# DEClampPanel.net
KiCad netlist of a schematic drawn in EAGLE
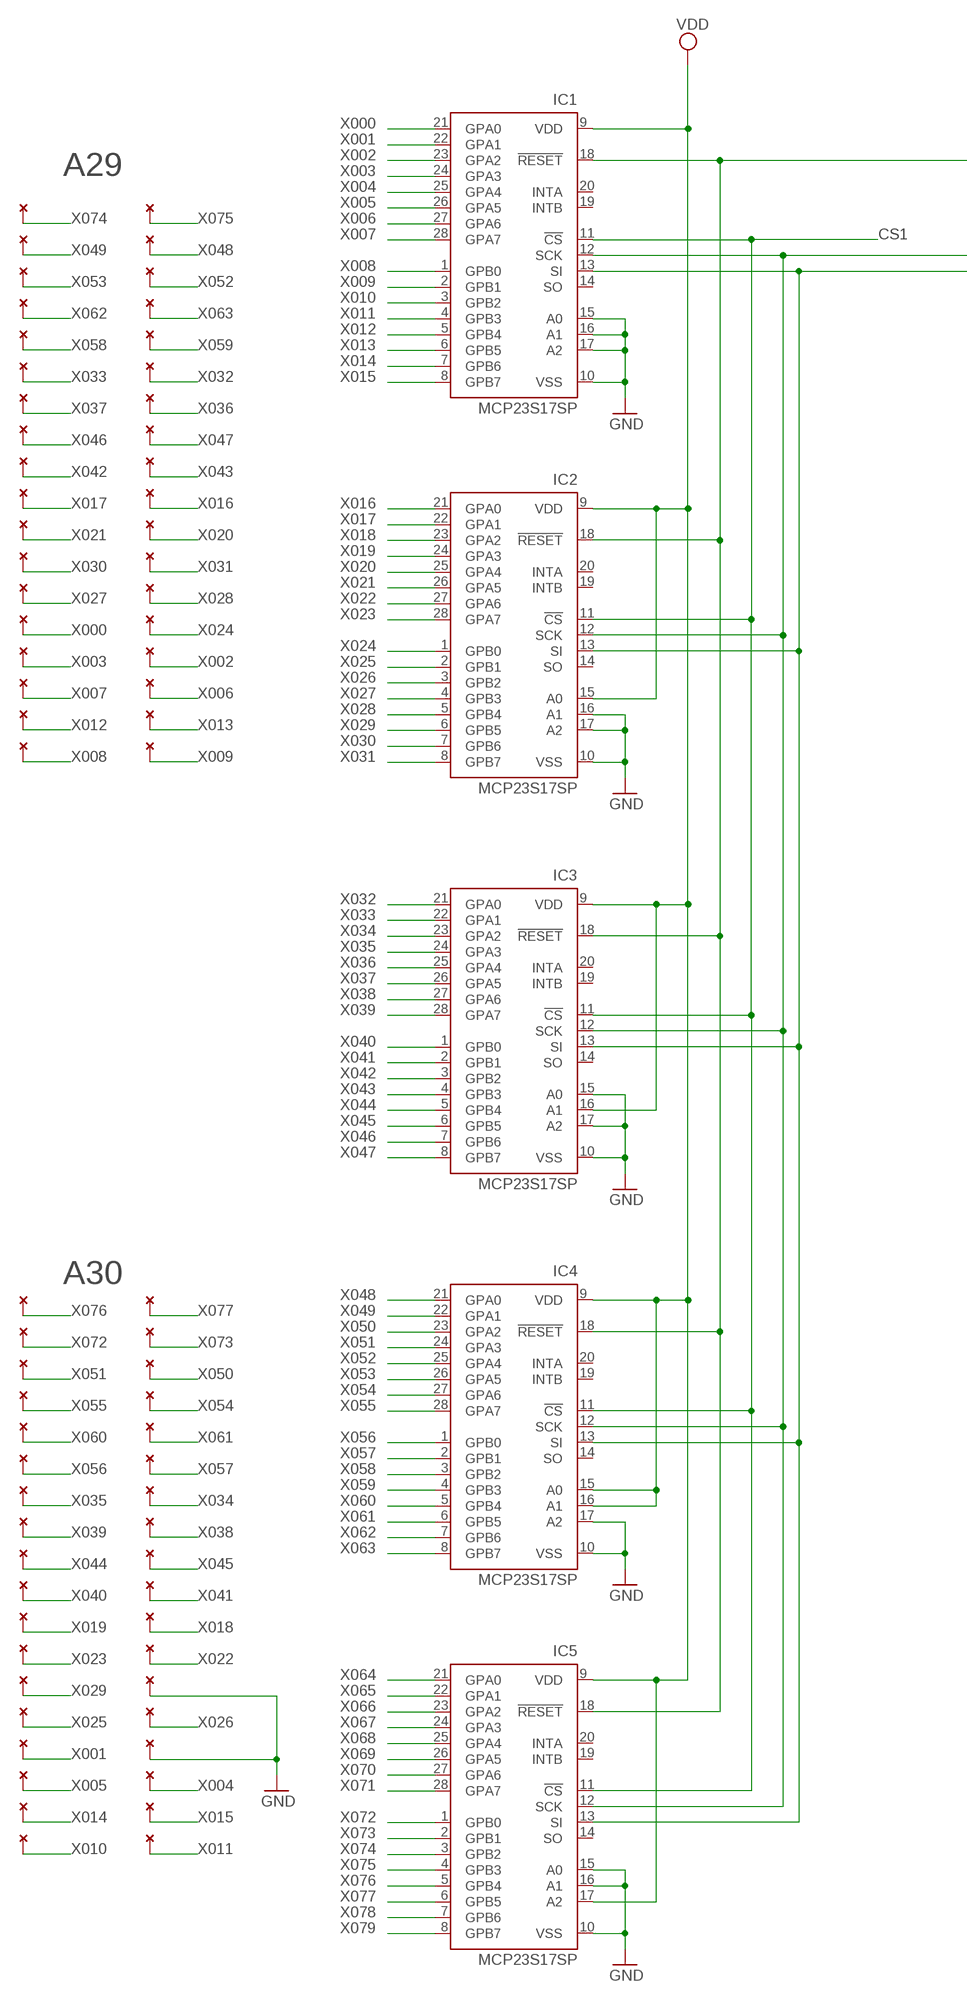
[diagram p0: schematic, sheet 1, part 1 of 2]
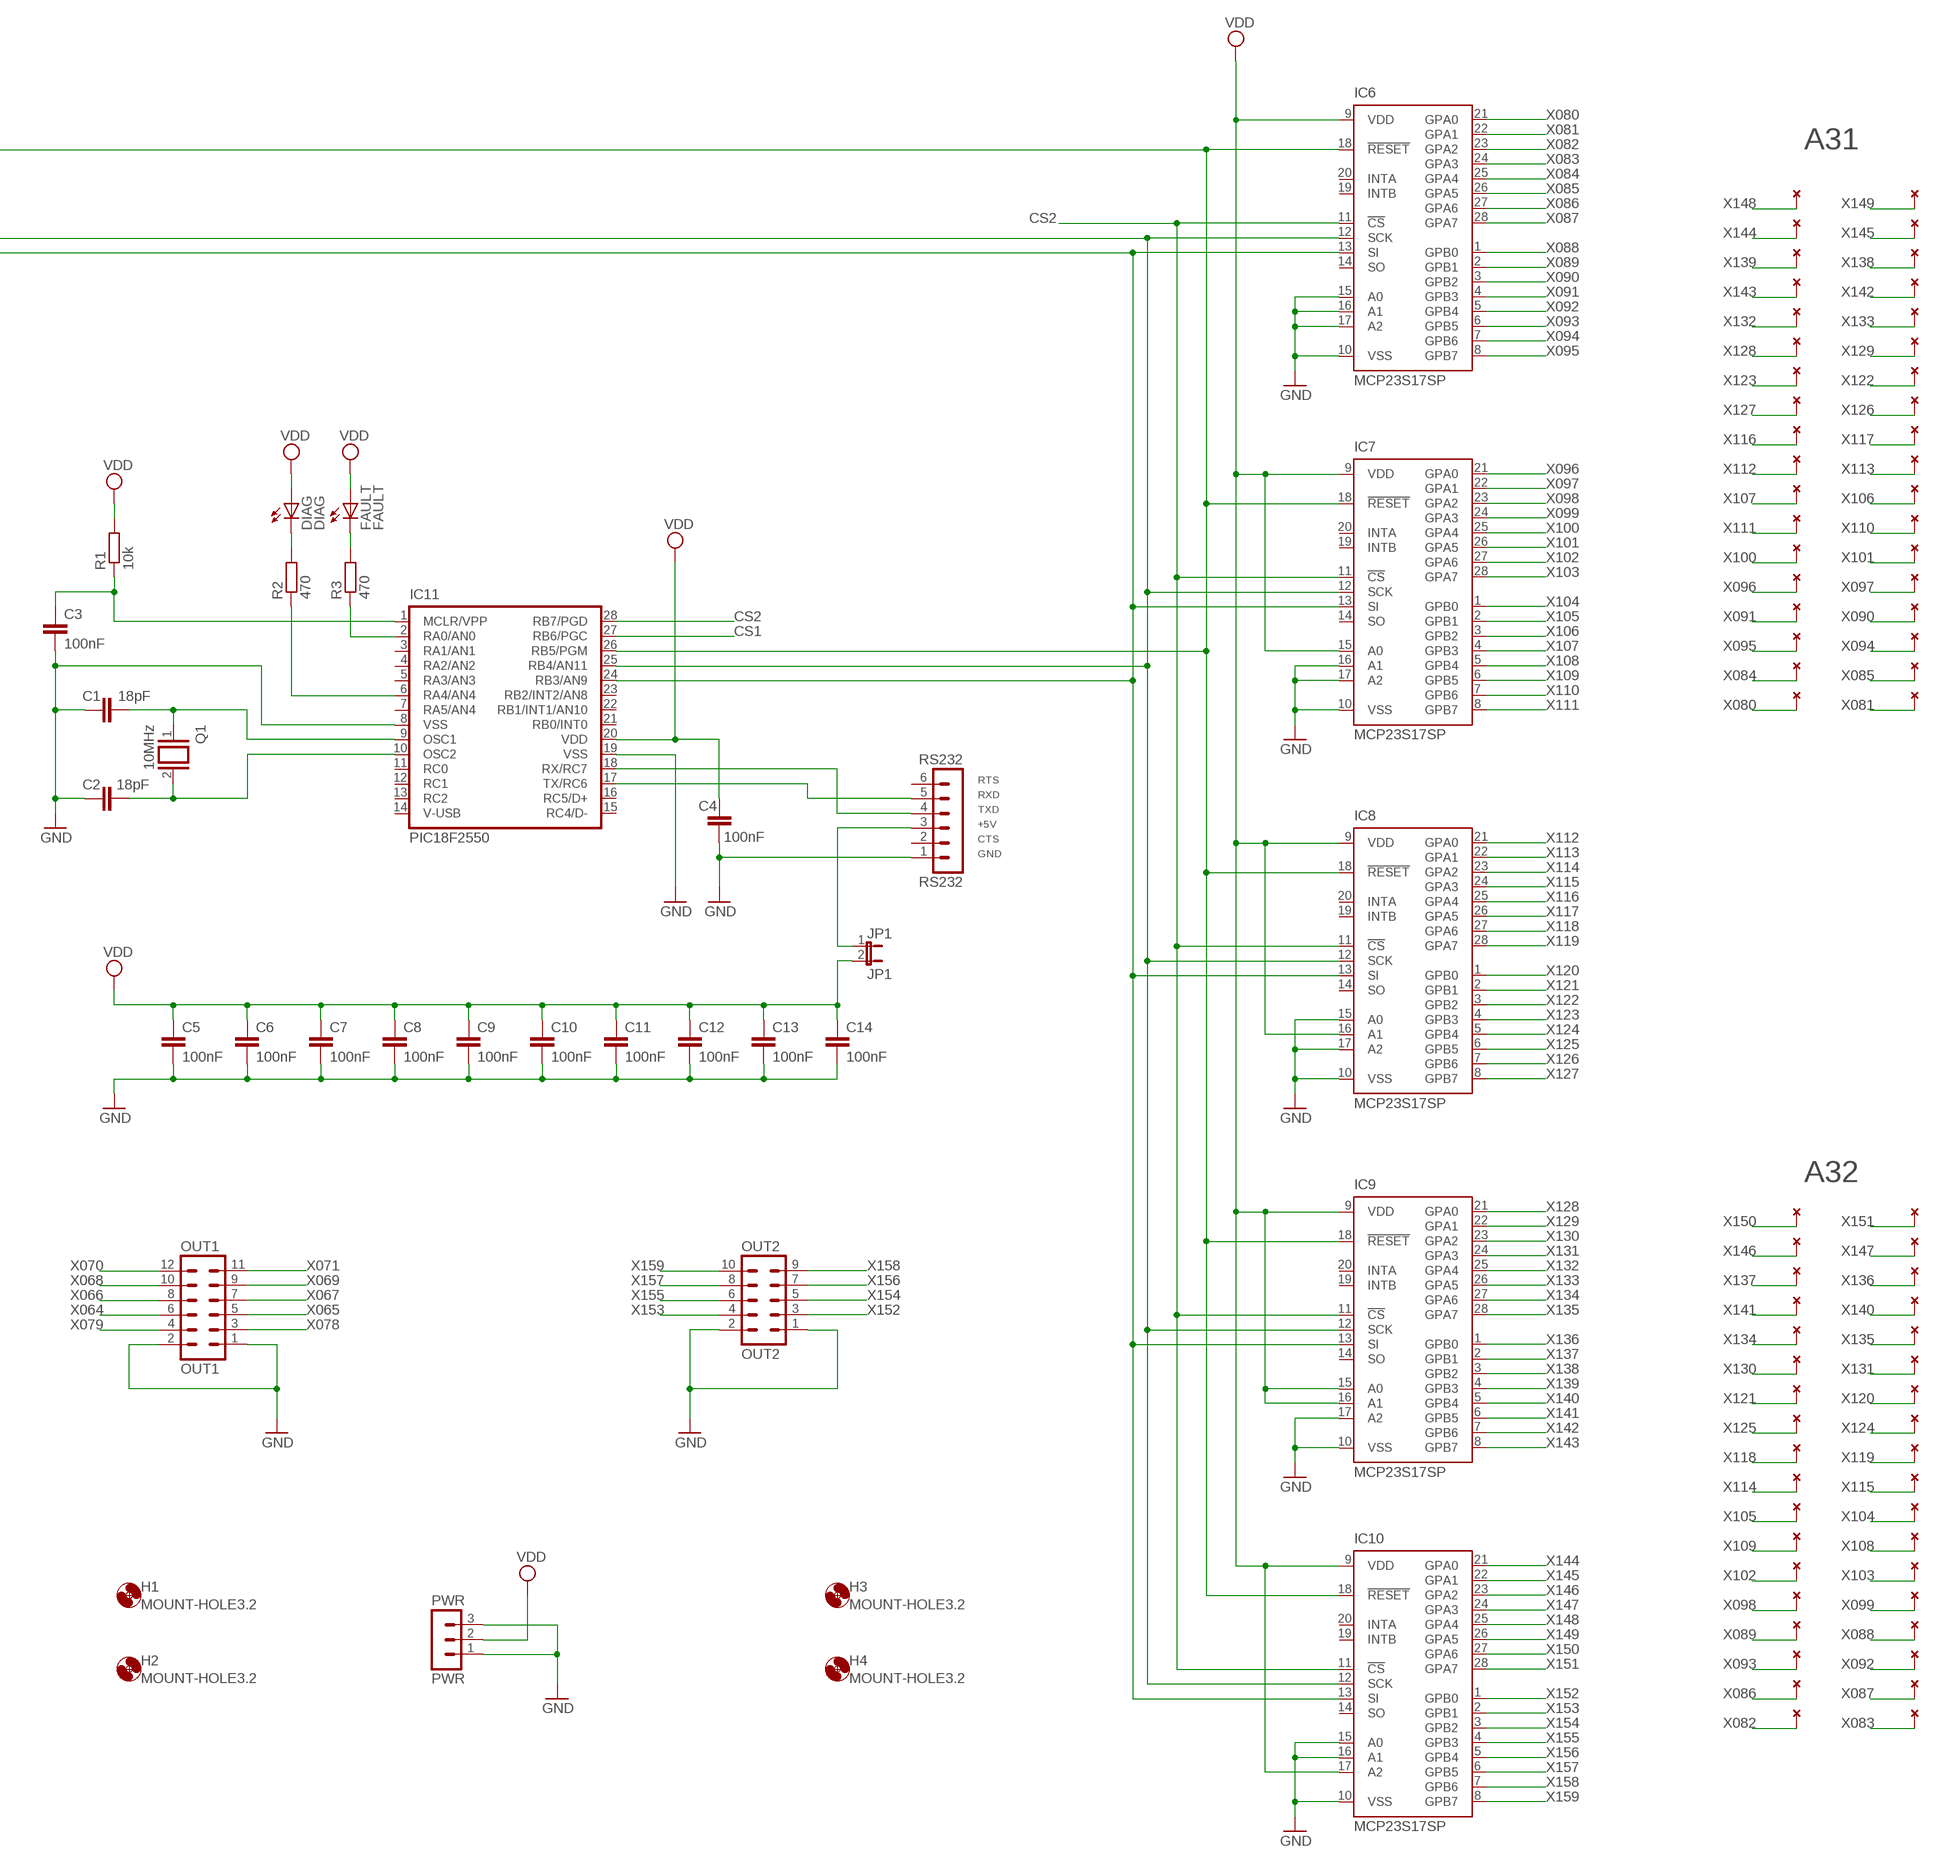
[diagram p1: schematic, sheet 1, part 2 of 2]

(export (version "E")
  (design (tool "Eeschema 10.0.6"))
  (components
    (comp (ref "A29")
      (value "THRU-HOLE2W")
      (footprint "eagle-import:THRU-HOLE2")
      (libsource (lib "eagle-import") (part "THRU-HOLE2W"))
    )
    (comp (ref "A30")
      (value "THRU-HOLE2W")
      (footprint "eagle-import:THRU-HOLE2")
      (libsource (lib "eagle-import") (part "THRU-HOLE2W"))
    )
    (comp (ref "A31")
      (value "THRU-HOLE2W")
      (footprint "eagle-import:THRU-HOLE2")
      (libsource (lib "eagle-import") (part "THRU-HOLE2W"))
    )
    (comp (ref "A32")
      (value "THRU-HOLE2W")
      (footprint "eagle-import:THRU-HOLE2")
      (libsource (lib "eagle-import") (part "THRU-HOLE2W"))
    )
    (comp (ref "C1")
      (value "18pF")
      (footprint "eagle-import:C025-025X050")
      (libsource (lib "eagle-import") (part "C-EU025-025X050"))
    )
    (comp (ref "C2")
      (value "18pF")
      (footprint "eagle-import:C025-025X050")
      (libsource (lib "eagle-import") (part "C-EU025-025X050"))
    )
    (comp (ref "C3")
      (value "100nF")
      (footprint "eagle-import:C025-025X050")
      (libsource (lib "eagle-import") (part "C-EU025-025X050"))
    )
    (comp (ref "C4")
      (value "100nF")
      (footprint "eagle-import:C025-025X050")
      (libsource (lib "eagle-import") (part "C-EU025-025X050"))
    )
    (comp (ref "C5")
      (value "100nF")
      (footprint "eagle-import:C025-025X050")
      (libsource (lib "eagle-import") (part "C-EU025-025X050"))
    )
    (comp (ref "C6")
      (value "100nF")
      (footprint "eagle-import:C025-025X050")
      (libsource (lib "eagle-import") (part "C-EU025-025X050"))
    )
    (comp (ref "C7")
      (value "100nF")
      (footprint "eagle-import:C025-025X050")
      (libsource (lib "eagle-import") (part "C-EU025-025X050"))
    )
    (comp (ref "C8")
      (value "100nF")
      (footprint "eagle-import:C025-025X050")
      (libsource (lib "eagle-import") (part "C-EU025-025X050"))
    )
    (comp (ref "C9")
      (value "100nF")
      (footprint "eagle-import:C025-025X050")
      (libsource (lib "eagle-import") (part "C-EU025-025X050"))
    )
    (comp (ref "C10")
      (value "100nF")
      (footprint "eagle-import:C025-025X050")
      (libsource (lib "eagle-import") (part "C-EU025-025X050"))
    )
    (comp (ref "C11")
      (value "100nF")
      (footprint "eagle-import:C025-025X050")
      (libsource (lib "eagle-import") (part "C-EU025-025X050"))
    )
    (comp (ref "C12")
      (value "100nF")
      (footprint "eagle-import:C025-025X050")
      (libsource (lib "eagle-import") (part "C-EU025-025X050"))
    )
    (comp (ref "C13")
      (value "100nF")
      (footprint "eagle-import:C025-025X050")
      (libsource (lib "eagle-import") (part "C-EU025-025X050"))
    )
    (comp (ref "C14")
      (value "100nF")
      (footprint "eagle-import:C025-025X050")
      (libsource (lib "eagle-import") (part "C-EU025-025X050"))
    )
    (comp (ref "DIAG")
      (value "DIAG")
      (footprint "eagle-import:LED3MM")
      (libsource (lib "eagle-import") (part "LED3MM"))
    )
    (comp (ref "FAULT")
      (value "FAULT")
      (footprint "eagle-import:LED3MM")
      (libsource (lib "eagle-import") (part "LED3MM"))
    )
    (comp (ref "H1")
      (value "MOUNT-HOLE3.2")
      (footprint "eagle-import:3,2")
      (libsource (lib "eagle-import") (part "MOUNT-HOLE3.2"))
    )
    (comp (ref "H2")
      (value "MOUNT-HOLE3.2")
      (footprint "eagle-import:3,2")
      (libsource (lib "eagle-import") (part "MOUNT-HOLE3.2"))
    )
    (comp (ref "H3")
      (value "MOUNT-HOLE3.2")
      (footprint "eagle-import:3,2")
      (libsource (lib "eagle-import") (part "MOUNT-HOLE3.2"))
    )
    (comp (ref "H4")
      (value "MOUNT-HOLE3.2")
      (footprint "eagle-import:3,2")
      (libsource (lib "eagle-import") (part "MOUNT-HOLE3.2"))
    )
    (comp (ref "IC1")
      (value "MCP23S17SP")
      (footprint "eagle-import:DIL28-3")
      (fields (field (name "MF") "MICROCHIP") (field (name "MPN") "MCP23S17-E/SP"))
      (libsource (lib "eagle-import") (part "MCP23S17SP"))
    )
    (comp (ref "IC2")
      (value "MCP23S17SP")
      (footprint "eagle-import:DIL28-3")
      (fields (field (name "MF") "MICROCHIP") (field (name "MPN") "MCP23S17-E/SP"))
      (libsource (lib "eagle-import") (part "MCP23S17SP"))
    )
    (comp (ref "IC3")
      (value "MCP23S17SP")
      (footprint "eagle-import:DIL28-3")
      (fields (field (name "MF") "MICROCHIP") (field (name "MPN") "MCP23S17-E/SP"))
      (libsource (lib "eagle-import") (part "MCP23S17SP"))
    )
    (comp (ref "IC4")
      (value "MCP23S17SP")
      (footprint "eagle-import:DIL28-3")
      (fields (field (name "MF") "MICROCHIP") (field (name "MPN") "MCP23S17-E/SP"))
      (libsource (lib "eagle-import") (part "MCP23S17SP"))
    )
    (comp (ref "IC5")
      (value "MCP23S17SP")
      (footprint "eagle-import:DIL28-3")
      (fields (field (name "MF") "MICROCHIP") (field (name "MPN") "MCP23S17-E/SP"))
      (libsource (lib "eagle-import") (part "MCP23S17SP"))
    )
    (comp (ref "IC6")
      (value "MCP23S17SP")
      (footprint "eagle-import:DIL28-3")
      (fields (field (name "MF") "MICROCHIP") (field (name "MPN") "MCP23S17-E/SP"))
      (libsource (lib "eagle-import") (part "MCP23S17SP"))
    )
    (comp (ref "IC7")
      (value "MCP23S17SP")
      (footprint "eagle-import:DIL28-3")
      (fields (field (name "MF") "MICROCHIP") (field (name "MPN") "MCP23S17-E/SP"))
      (libsource (lib "eagle-import") (part "MCP23S17SP"))
    )
    (comp (ref "IC8")
      (value "MCP23S17SP")
      (footprint "eagle-import:DIL28-3")
      (fields (field (name "MF") "MICROCHIP") (field (name "MPN") "MCP23S17-E/SP"))
      (libsource (lib "eagle-import") (part "MCP23S17SP"))
    )
    (comp (ref "IC9")
      (value "MCP23S17SP")
      (footprint "eagle-import:DIL28-3")
      (fields (field (name "MF") "MICROCHIP") (field (name "MPN") "MCP23S17-E/SP"))
      (libsource (lib "eagle-import") (part "MCP23S17SP"))
    )
    (comp (ref "IC10")
      (value "MCP23S17SP")
      (footprint "eagle-import:DIL28-3")
      (fields (field (name "MF") "MICROCHIP") (field (name "MPN") "MCP23S17-E/SP"))
      (libsource (lib "eagle-import") (part "MCP23S17SP"))
    )
    (comp (ref "IC11")
      (value "PIC18F2550")
      (footprint "eagle-import:DIL28-3")
      (libsource (lib "eagle-import") (part "PIC18F2550"))
    )
    (comp (ref "JP1")
      (value "JP1")
      (footprint "eagle-import:1X02")
      (libsource (lib "eagle-import") (part "JUMPER-2PTH"))
    )
    (comp (ref "OUT1")
      (value "OUT1")
      (footprint "eagle-import:MA06-2")
      (libsource (lib "eagle-import") (part "MA06-2"))
    )
    (comp (ref "OUT2")
      (value "OUT2")
      (footprint "eagle-import:MA05-2")
      (libsource (lib "eagle-import") (part "MA05-2"))
    )
    (comp (ref "PWR")
      (value "PWR")
      (footprint "eagle-import:MA03-1")
      (libsource (lib "eagle-import") (part "MA03-1"))
    )
    (comp (ref "Q1")
      (value "10MHz")
      (footprint "eagle-import:QS")
      (libsource (lib "eagle-import") (part "XTAL/S"))
    )
    (comp (ref "R1")
      (value "10k")
      (footprint "eagle-import:0204_7")
      (libsource (lib "eagle-import") (part "R-EU_0204/7"))
    )
    (comp (ref "R2")
      (value "470")
      (footprint "eagle-import:0204_7")
      (libsource (lib "eagle-import") (part "R-EU_0204/7"))
    )
    (comp (ref "R3")
      (value "470")
      (footprint "eagle-import:0204_7")
      (libsource (lib "eagle-import") (part "R-EU_0204/7"))
    )
    (comp (ref "RS232")
      (value "RS232")
      (footprint "eagle-import:MA06-1")
      (libsource (lib "eagle-import") (part "MA06-1"))
    )
  )
  (nets
    (net (code "1") (name "/CS1") (class "Default")
      (node (ref "IC1") (pin "11") (pinfunction "~{CS}_11") (pintype "input"))
      (node (ref "IC11") (pin "27") (pinfunction "RB6/PGC_27") (pintype "bidirectional"))
      (node (ref "IC2") (pin "11") (pinfunction "~{CS}_11") (pintype "input"))
      (node (ref "IC3") (pin "11") (pinfunction "~{CS}_11") (pintype "input"))
      (node (ref "IC4") (pin "11") (pinfunction "~{CS}_11") (pintype "input"))
      (node (ref "IC5") (pin "11") (pinfunction "~{CS}_11") (pintype "input"))
    )
    (net (code "2") (name "/CS2") (class "Default")
      (node (ref "IC10") (pin "11") (pinfunction "~{CS}_11") (pintype "input"))
      (node (ref "IC11") (pin "28") (pinfunction "RB7/PGD_28") (pintype "bidirectional"))
      (node (ref "IC6") (pin "11") (pinfunction "~{CS}_11") (pintype "input"))
      (node (ref "IC7") (pin "11") (pinfunction "~{CS}_11") (pintype "input"))
      (node (ref "IC8") (pin "11") (pinfunction "~{CS}_11") (pintype "input"))
      (node (ref "IC9") (pin "11") (pinfunction "~{CS}_11") (pintype "input"))
    )
    (net (code "3") (name "/X000") (class "Default")
      (node (ref "A29") (pin "E1") (pinfunction "P$1_E1") (pintype "passive"))
      (node (ref "IC1") (pin "21") (pinfunction "GPA0_21") (pintype "bidirectional"))
    )
    (net (code "4") (name "/X001") (class "Default")
      (node (ref "A30") (pin "D1") (pinfunction "P$1_D1") (pintype "passive"))
      (node (ref "IC1") (pin "22") (pinfunction "GPA1_22") (pintype "bidirectional"))
    )
    (net (code "5") (name "/X002") (class "Default")
      (node (ref "A29") (pin "D2") (pinfunction "P$1_D2") (pintype "passive"))
      (node (ref "IC1") (pin "23") (pinfunction "GPA2_23") (pintype "bidirectional"))
    )
    (net (code "6") (name "/X003") (class "Default")
      (node (ref "A29") (pin "D1") (pinfunction "P$1_D1") (pintype "passive"))
      (node (ref "IC1") (pin "24") (pinfunction "GPA3_24") (pintype "bidirectional"))
    )
    (net (code "7") (name "/X004") (class "Default")
      (node (ref "A30") (pin "C2") (pinfunction "P$1_C2") (pintype "passive"))
      (node (ref "IC1") (pin "25") (pinfunction "GPA4_25") (pintype "bidirectional"))
    )
    (net (code "8") (name "/X005") (class "Default")
      (node (ref "A30") (pin "C1") (pinfunction "P$1_C1") (pintype "passive"))
      (node (ref "IC1") (pin "26") (pinfunction "GPA5_26") (pintype "bidirectional"))
    )
    (net (code "9") (name "/X006") (class "Default")
      (node (ref "A29") (pin "C2") (pinfunction "P$1_C2") (pintype "passive"))
      (node (ref "IC1") (pin "27") (pinfunction "GPA6_27") (pintype "bidirectional"))
    )
    (net (code "10") (name "/X007") (class "Default")
      (node (ref "A29") (pin "C1") (pinfunction "P$1_C1") (pintype "passive"))
      (node (ref "IC1") (pin "28") (pinfunction "GPA7_28") (pintype "bidirectional"))
    )
    (net (code "11") (name "/X008") (class "Default")
      (node (ref "A29") (pin "A1") (pinfunction "P$1_A1") (pintype "passive"))
      (node (ref "IC1") (pin "1") (pinfunction "GPB0_1") (pintype "bidirectional"))
    )
    (net (code "12") (name "/X009") (class "Default")
      (node (ref "A29") (pin "A2") (pinfunction "P$1_A2") (pintype "passive"))
      (node (ref "IC1") (pin "2") (pinfunction "GPB1_2") (pintype "bidirectional"))
    )
    (net (code "13") (name "/X010") (class "Default")
      (node (ref "A30") (pin "A1") (pinfunction "P$1_A1") (pintype "passive"))
      (node (ref "IC1") (pin "3") (pinfunction "GPB2_3") (pintype "bidirectional"))
    )
    (net (code "14") (name "/X011") (class "Default")
      (node (ref "A30") (pin "A2") (pinfunction "P$1_A2") (pintype "passive"))
      (node (ref "IC1") (pin "4") (pinfunction "GPB3_4") (pintype "bidirectional"))
    )
    (net (code "15") (name "/X012") (class "Default")
      (node (ref "A29") (pin "B1") (pinfunction "P$1_B1") (pintype "passive"))
      (node (ref "IC1") (pin "5") (pinfunction "GPB4_5") (pintype "bidirectional"))
    )
    (net (code "16") (name "/X013") (class "Default")
      (node (ref "A29") (pin "B2") (pinfunction "P$1_B2") (pintype "passive"))
      (node (ref "IC1") (pin "6") (pinfunction "GPB5_6") (pintype "bidirectional"))
    )
    (net (code "17") (name "/X014") (class "Default")
      (node (ref "A30") (pin "B1") (pinfunction "P$1_B1") (pintype "passive"))
      (node (ref "IC1") (pin "7") (pinfunction "GPB6_7") (pintype "bidirectional"))
    )
    (net (code "18") (name "/X015") (class "Default")
      (node (ref "A30") (pin "B2") (pinfunction "P$1_B2") (pintype "passive"))
      (node (ref "IC1") (pin "8") (pinfunction "GPB7_8") (pintype "bidirectional"))
    )
    (net (code "19") (name "/X016") (class "Default")
      (node (ref "A29") (pin "K2") (pinfunction "P$1_K2") (pintype "passive"))
      (node (ref "IC2") (pin "21") (pinfunction "GPA0_21") (pintype "bidirectional"))
    )
    (net (code "20") (name "/X017") (class "Default")
      (node (ref "A29") (pin "K1") (pinfunction "P$1_K1") (pintype "passive"))
      (node (ref "IC2") (pin "22") (pinfunction "GPA1_22") (pintype "bidirectional"))
    )
    (net (code "21") (name "/X018") (class "Default")
      (node (ref "A30") (pin "J2") (pinfunction "P$1_J2") (pintype "passive"))
      (node (ref "IC2") (pin "23") (pinfunction "GPA2_23") (pintype "bidirectional"))
    )
    (net (code "22") (name "/X019") (class "Default")
      (node (ref "A30") (pin "J1") (pinfunction "P$1_J1") (pintype "passive"))
      (node (ref "IC2") (pin "24") (pinfunction "GPA3_24") (pintype "bidirectional"))
    )
    (net (code "23") (name "/X020") (class "Default")
      (node (ref "A29") (pin "J2") (pinfunction "P$1_J2") (pintype "passive"))
      (node (ref "IC2") (pin "25") (pinfunction "GPA4_25") (pintype "bidirectional"))
    )
    (net (code "24") (name "/X021") (class "Default")
      (node (ref "A29") (pin "J1") (pinfunction "P$1_J1") (pintype "passive"))
      (node (ref "IC2") (pin "26") (pinfunction "GPA5_26") (pintype "bidirectional"))
    )
    (net (code "25") (name "/X022") (class "Default")
      (node (ref "A30") (pin "H2") (pinfunction "P$1_H2") (pintype "passive"))
      (node (ref "IC2") (pin "27") (pinfunction "GPA6_27") (pintype "bidirectional"))
    )
    (net (code "26") (name "/X023") (class "Default")
      (node (ref "A30") (pin "H1") (pinfunction "P$1_H1") (pintype "passive"))
      (node (ref "IC2") (pin "28") (pinfunction "GPA7_28") (pintype "bidirectional"))
    )
    (net (code "27") (name "/X024") (class "Default")
      (node (ref "A29") (pin "E2") (pinfunction "P$1_E2") (pintype "passive"))
      (node (ref "IC2") (pin "1") (pinfunction "GPB0_1") (pintype "bidirectional"))
    )
    (net (code "28") (name "/X025") (class "Default")
      (node (ref "A30") (pin "E1") (pinfunction "P$1_E1") (pintype "passive"))
      (node (ref "IC2") (pin "2") (pinfunction "GPB1_2") (pintype "bidirectional"))
    )
    (net (code "29") (name "/X026") (class "Default")
      (node (ref "A30") (pin "E2") (pinfunction "P$1_E2") (pintype "passive"))
      (node (ref "IC2") (pin "3") (pinfunction "GPB2_3") (pintype "bidirectional"))
    )
    (net (code "30") (name "/X027") (class "Default")
      (node (ref "A29") (pin "F1") (pinfunction "P$1_F1") (pintype "passive"))
      (node (ref "IC2") (pin "4") (pinfunction "GPB3_4") (pintype "bidirectional"))
    )
    (net (code "31") (name "/X028") (class "Default")
      (node (ref "A29") (pin "F2") (pinfunction "P$1_F2") (pintype "passive"))
      (node (ref "IC2") (pin "5") (pinfunction "GPB4_5") (pintype "bidirectional"))
    )
    (net (code "32") (name "/X029") (class "Default")
      (node (ref "A30") (pin "F1") (pinfunction "P$1_F1") (pintype "passive"))
      (node (ref "IC2") (pin "6") (pinfunction "GPB5_6") (pintype "bidirectional"))
    )
    (net (code "33") (name "/X030") (class "Default")
      (node (ref "A29") (pin "H1") (pinfunction "P$1_H1") (pintype "passive"))
      (node (ref "IC2") (pin "7") (pinfunction "GPB6_7") (pintype "bidirectional"))
    )
    (net (code "34") (name "/X031") (class "Default")
      (node (ref "A29") (pin "H2") (pinfunction "P$1_H2") (pintype "passive"))
      (node (ref "IC2") (pin "8") (pinfunction "GPB7_8") (pintype "bidirectional"))
    )
    (net (code "35") (name "/X032") (class "Default")
      (node (ref "A29") (pin "P2") (pinfunction "P$1_P2") (pintype "passive"))
      (node (ref "IC3") (pin "21") (pinfunction "GPA0_21") (pintype "bidirectional"))
    )
    (net (code "36") (name "/X033") (class "Default")
      (node (ref "A29") (pin "P1") (pinfunction "P$1_P1") (pintype "passive"))
      (node (ref "IC3") (pin "22") (pinfunction "GPA1_22") (pintype "bidirectional"))
    )
    (net (code "37") (name "/X034") (class "Default")
      (node (ref "A30") (pin "N2") (pinfunction "P$1_N2") (pintype "passive"))
      (node (ref "IC3") (pin "23") (pinfunction "GPA2_23") (pintype "bidirectional"))
    )
    (net (code "38") (name "/X035") (class "Default")
      (node (ref "A30") (pin "N1") (pinfunction "P$1_N1") (pintype "passive"))
      (node (ref "IC3") (pin "24") (pinfunction "GPA3_24") (pintype "bidirectional"))
    )
    (net (code "39") (name "/X036") (class "Default")
      (node (ref "A29") (pin "N2") (pinfunction "P$1_N2") (pintype "passive"))
      (node (ref "IC3") (pin "25") (pinfunction "GPA4_25") (pintype "bidirectional"))
    )
    (net (code "40") (name "/X037") (class "Default")
      (node (ref "A29") (pin "N1") (pinfunction "P$1_N1") (pintype "passive"))
      (node (ref "IC3") (pin "26") (pinfunction "GPA5_26") (pintype "bidirectional"))
    )
    (net (code "41") (name "/X038") (class "Default")
      (node (ref "A30") (pin "M2") (pinfunction "P$1_M2") (pintype "passive"))
      (node (ref "IC3") (pin "27") (pinfunction "GPA6_27") (pintype "bidirectional"))
    )
    (net (code "42") (name "/X039") (class "Default")
      (node (ref "A30") (pin "M1") (pinfunction "P$1_M1") (pintype "passive"))
      (node (ref "IC3") (pin "28") (pinfunction "GPA7_28") (pintype "bidirectional"))
    )
    (net (code "43") (name "/X040") (class "Default")
      (node (ref "A30") (pin "K1") (pinfunction "P$1_K1") (pintype "passive"))
      (node (ref "IC3") (pin "1") (pinfunction "GPB0_1") (pintype "bidirectional"))
    )
    (net (code "44") (name "/X041") (class "Default")
      (node (ref "A30") (pin "K2") (pinfunction "P$1_K2") (pintype "passive"))
      (node (ref "IC3") (pin "2") (pinfunction "GPB1_2") (pintype "bidirectional"))
    )
    (net (code "45") (name "/X042") (class "Default")
      (node (ref "A29") (pin "L1") (pinfunction "P$1_L1") (pintype "passive"))
      (node (ref "IC3") (pin "3") (pinfunction "GPB2_3") (pintype "bidirectional"))
    )
    (net (code "46") (name "/X043") (class "Default")
      (node (ref "A29") (pin "L2") (pinfunction "P$1_L2") (pintype "passive"))
      (node (ref "IC3") (pin "4") (pinfunction "GPB3_4") (pintype "bidirectional"))
    )
    (net (code "47") (name "/X044") (class "Default")
      (node (ref "A30") (pin "L1") (pinfunction "P$1_L1") (pintype "passive"))
      (node (ref "IC3") (pin "5") (pinfunction "GPB4_5") (pintype "bidirectional"))
    )
    (net (code "48") (name "/X045") (class "Default")
      (node (ref "A30") (pin "L2") (pinfunction "P$1_L2") (pintype "passive"))
      (node (ref "IC3") (pin "6") (pinfunction "GPB5_6") (pintype "bidirectional"))
    )
    (net (code "49") (name "/X046") (class "Default")
      (node (ref "A29") (pin "M1") (pinfunction "P$1_M1") (pintype "passive"))
      (node (ref "IC3") (pin "7") (pinfunction "GPB6_7") (pintype "bidirectional"))
    )
    (net (code "50") (name "/X047") (class "Default")
      (node (ref "A29") (pin "M2") (pinfunction "P$1_M2") (pintype "passive"))
      (node (ref "IC3") (pin "8") (pinfunction "GPB7_8") (pintype "bidirectional"))
    )
    (net (code "51") (name "/X048") (class "Default")
      (node (ref "A29") (pin "U2") (pinfunction "P$1_U2") (pintype "passive"))
      (node (ref "IC4") (pin "21") (pinfunction "GPA0_21") (pintype "bidirectional"))
    )
    (net (code "52") (name "/X049") (class "Default")
      (node (ref "A29") (pin "U1") (pinfunction "P$1_U1") (pintype "passive"))
      (node (ref "IC4") (pin "22") (pinfunction "GPA1_22") (pintype "bidirectional"))
    )
    (net (code "53") (name "/X050") (class "Default")
      (node (ref "A30") (pin "T2") (pinfunction "P$1_T2") (pintype "passive"))
      (node (ref "IC4") (pin "23") (pinfunction "GPA2_23") (pintype "bidirectional"))
    )
    (net (code "54") (name "/X051") (class "Default")
      (node (ref "A30") (pin "T1") (pinfunction "P$1_T1") (pintype "passive"))
      (node (ref "IC4") (pin "24") (pinfunction "GPA3_24") (pintype "bidirectional"))
    )
    (net (code "55") (name "/X052") (class "Default")
      (node (ref "A29") (pin "T2") (pinfunction "P$1_T2") (pintype "passive"))
      (node (ref "IC4") (pin "25") (pinfunction "GPA4_25") (pintype "bidirectional"))
    )
    (net (code "56") (name "/X053") (class "Default")
      (node (ref "A29") (pin "T1") (pinfunction "P$1_T1") (pintype "passive"))
      (node (ref "IC4") (pin "26") (pinfunction "GPA5_26") (pintype "bidirectional"))
    )
    (net (code "57") (name "/X054") (class "Default")
      (node (ref "A30") (pin "S2") (pinfunction "P$1_S2") (pintype "passive"))
      (node (ref "IC4") (pin "27") (pinfunction "GPA6_27") (pintype "bidirectional"))
    )
    (net (code "58") (name "/X055") (class "Default")
      (node (ref "A30") (pin "S1") (pinfunction "P$1_S1") (pintype "passive"))
      (node (ref "IC4") (pin "28") (pinfunction "GPA7_28") (pintype "bidirectional"))
    )
    (net (code "59") (name "/X056") (class "Default")
      (node (ref "A30") (pin "P1") (pinfunction "P$1_P1") (pintype "passive"))
      (node (ref "IC4") (pin "1") (pinfunction "GPB0_1") (pintype "bidirectional"))
    )
    (net (code "60") (name "/X057") (class "Default")
      (node (ref "A30") (pin "P2") (pinfunction "P$1_P2") (pintype "passive"))
      (node (ref "IC4") (pin "2") (pinfunction "GPB1_2") (pintype "bidirectional"))
    )
    (net (code "61") (name "/X058") (class "Default")
      (node (ref "A29") (pin "R1") (pinfunction "P$1_R1") (pintype "passive"))
      (node (ref "IC4") (pin "3") (pinfunction "GPB2_3") (pintype "bidirectional"))
    )
    (net (code "62") (name "/X059") (class "Default")
      (node (ref "A29") (pin "R2") (pinfunction "P$1_R2") (pintype "passive"))
      (node (ref "IC4") (pin "4") (pinfunction "GPB3_4") (pintype "bidirectional"))
    )
    (net (code "63") (name "/X060") (class "Default")
      (node (ref "A30") (pin "R1") (pinfunction "P$1_R1") (pintype "passive"))
      (node (ref "IC4") (pin "5") (pinfunction "GPB4_5") (pintype "bidirectional"))
    )
    (net (code "64") (name "/X061") (class "Default")
      (node (ref "A30") (pin "R2") (pinfunction "P$1_R2") (pintype "passive"))
      (node (ref "IC4") (pin "6") (pinfunction "GPB5_6") (pintype "bidirectional"))
    )
    (net (code "65") (name "/X062") (class "Default")
      (node (ref "A29") (pin "S1") (pinfunction "P$1_S1") (pintype "passive"))
      (node (ref "IC4") (pin "7") (pinfunction "GPB6_7") (pintype "bidirectional"))
    )
    (net (code "66") (name "/X063") (class "Default")
      (node (ref "A29") (pin "S2") (pinfunction "P$1_S2") (pintype "passive"))
      (node (ref "IC4") (pin "8") (pinfunction "GPB7_8") (pintype "bidirectional"))
    )
    (net (code "67") (name "/X064") (class "Default")
      (node (ref "IC5") (pin "21") (pinfunction "GPA0_21") (pintype "bidirectional"))
      (node (ref "OUT1") (pin "6") (pinfunction "6_6") (pintype "passive"))
    )
    (net (code "68") (name "/X065") (class "Default")
      (node (ref "IC5") (pin "22") (pinfunction "GPA1_22") (pintype "bidirectional"))
      (node (ref "OUT1") (pin "5") (pinfunction "5_5") (pintype "passive"))
    )
    (net (code "69") (name "/X066") (class "Default")
      (node (ref "IC5") (pin "23") (pinfunction "GPA2_23") (pintype "bidirectional"))
      (node (ref "OUT1") (pin "8") (pinfunction "8_8") (pintype "passive"))
    )
    (net (code "70") (name "/X067") (class "Default")
      (node (ref "IC5") (pin "24") (pinfunction "GPA3_24") (pintype "bidirectional"))
      (node (ref "OUT1") (pin "7") (pinfunction "7_7") (pintype "passive"))
    )
    (net (code "71") (name "/X068") (class "Default")
      (node (ref "IC5") (pin "25") (pinfunction "GPA4_25") (pintype "bidirectional"))
      (node (ref "OUT1") (pin "10") (pinfunction "10_10") (pintype "passive"))
    )
    (net (code "72") (name "/X069") (class "Default")
      (node (ref "IC5") (pin "26") (pinfunction "GPA5_26") (pintype "bidirectional"))
      (node (ref "OUT1") (pin "9") (pinfunction "9_9") (pintype "passive"))
    )
    (net (code "73") (name "/X070") (class "Default")
      (node (ref "IC5") (pin "27") (pinfunction "GPA6_27") (pintype "bidirectional"))
      (node (ref "OUT1") (pin "12") (pinfunction "12_12") (pintype "passive"))
    )
    (net (code "74") (name "/X071") (class "Default")
      (node (ref "IC5") (pin "28") (pinfunction "GPA7_28") (pintype "bidirectional"))
      (node (ref "OUT1") (pin "11") (pinfunction "11_11") (pintype "passive"))
    )
    (net (code "75") (name "/X072") (class "Default")
      (node (ref "A30") (pin "U1") (pinfunction "P$1_U1") (pintype "passive"))
      (node (ref "IC5") (pin "1") (pinfunction "GPB0_1") (pintype "bidirectional"))
    )
    (net (code "76") (name "/X073") (class "Default")
      (node (ref "A30") (pin "U2") (pinfunction "P$1_U2") (pintype "passive"))
      (node (ref "IC5") (pin "2") (pinfunction "GPB1_2") (pintype "bidirectional"))
    )
    (net (code "77") (name "/X074") (class "Default")
      (node (ref "A29") (pin "V1") (pinfunction "P$1_V1") (pintype "passive"))
      (node (ref "IC5") (pin "3") (pinfunction "GPB2_3") (pintype "bidirectional"))
    )
    (net (code "78") (name "/X075") (class "Default")
      (node (ref "A29") (pin "V2") (pinfunction "P$1_V2") (pintype "passive"))
      (node (ref "IC5") (pin "4") (pinfunction "GPB3_4") (pintype "bidirectional"))
    )
    (net (code "79") (name "/X076") (class "Default")
      (node (ref "A30") (pin "V1") (pinfunction "P$1_V1") (pintype "passive"))
      (node (ref "IC5") (pin "5") (pinfunction "GPB4_5") (pintype "bidirectional"))
    )
    (net (code "80") (name "/X077") (class "Default")
      (node (ref "A30") (pin "V2") (pinfunction "P$1_V2") (pintype "passive"))
      (node (ref "IC5") (pin "6") (pinfunction "GPB5_6") (pintype "bidirectional"))
    )
    (net (code "81") (name "/X078") (class "Default")
      (node (ref "IC5") (pin "7") (pinfunction "GPB6_7") (pintype "bidirectional"))
      (node (ref "OUT1") (pin "3") (pinfunction "3_3") (pintype "passive"))
    )
    (net (code "82") (name "/X079") (class "Default")
      (node (ref "IC5") (pin "8") (pinfunction "GPB7_8") (pintype "bidirectional"))
      (node (ref "OUT1") (pin "4") (pinfunction "4_4") (pintype "passive"))
    )
    (net (code "83") (name "/X080") (class "Default")
      (node (ref "A31") (pin "A1") (pinfunction "P$1_A1") (pintype "passive"))
      (node (ref "IC6") (pin "21") (pinfunction "GPA0_21") (pintype "bidirectional"))
    )
    (net (code "84") (name "/X081") (class "Default")
      (node (ref "A31") (pin "A2") (pinfunction "P$1_A2") (pintype "passive"))
      (node (ref "IC6") (pin "22") (pinfunction "GPA1_22") (pintype "bidirectional"))
    )
    (net (code "85") (name "/X082") (class "Default")
      (node (ref "A32") (pin "A1") (pinfunction "P$1_A1") (pintype "passive"))
      (node (ref "IC6") (pin "23") (pinfunction "GPA2_23") (pintype "bidirectional"))
    )
    (net (code "86") (name "/X083") (class "Default")
      (node (ref "A32") (pin "A2") (pinfunction "P$1_A2") (pintype "passive"))
      (node (ref "IC6") (pin "24") (pinfunction "GPA3_24") (pintype "bidirectional"))
    )
    (net (code "87") (name "/X084") (class "Default")
      (node (ref "A31") (pin "B1") (pinfunction "P$1_B1") (pintype "passive"))
      (node (ref "IC6") (pin "25") (pinfunction "GPA4_25") (pintype "bidirectional"))
    )
    (net (code "88") (name "/X085") (class "Default")
      (node (ref "A31") (pin "B2") (pinfunction "P$1_B2") (pintype "passive"))
      (node (ref "IC6") (pin "26") (pinfunction "GPA5_26") (pintype "bidirectional"))
    )
    (net (code "89") (name "/X086") (class "Default")
      (node (ref "A32") (pin "B1") (pinfunction "P$1_B1") (pintype "passive"))
      (node (ref "IC6") (pin "27") (pinfunction "GPA6_27") (pintype "bidirectional"))
    )
    (net (code "90") (name "/X087") (class "Default")
      (node (ref "A32") (pin "B2") (pinfunction "P$1_B2") (pintype "passive"))
      (node (ref "IC6") (pin "28") (pinfunction "GPA7_28") (pintype "bidirectional"))
    )
    (net (code "91") (name "/X088") (class "Default")
      (node (ref "A32") (pin "D2") (pinfunction "P$1_D2") (pintype "passive"))
      (node (ref "IC6") (pin "1") (pinfunction "GPB0_1") (pintype "bidirectional"))
    )
    (net (code "92") (name "/X089") (class "Default")
      (node (ref "A32") (pin "D1") (pinfunction "P$1_D1") (pintype "passive"))
      (node (ref "IC6") (pin "2") (pinfunction "GPB1_2") (pintype "bidirectional"))
    )
    (net (code "93") (name "/X090") (class "Default")
      (node (ref "A31") (pin "D2") (pinfunction "P$1_D2") (pintype "passive"))
      (node (ref "IC6") (pin "3") (pinfunction "GPB2_3") (pintype "bidirectional"))
    )
    (net (code "94") (name "/X091") (class "Default")
      (node (ref "A31") (pin "D1") (pinfunction "P$1_D1") (pintype "passive"))
      (node (ref "IC6") (pin "4") (pinfunction "GPB3_4") (pintype "bidirectional"))
    )
    (net (code "95") (name "/X092") (class "Default")
      (node (ref "A32") (pin "C2") (pinfunction "P$1_C2") (pintype "passive"))
      (node (ref "IC6") (pin "5") (pinfunction "GPB4_5") (pintype "bidirectional"))
    )
    (net (code "96") (name "/X093") (class "Default")
      (node (ref "A32") (pin "C1") (pinfunction "P$1_C1") (pintype "passive"))
      (node (ref "IC6") (pin "6") (pinfunction "GPB5_6") (pintype "bidirectional"))
    )
    (net (code "97") (name "/X094") (class "Default")
      (node (ref "A31") (pin "C2") (pinfunction "P$1_C2") (pintype "passive"))
      (node (ref "IC6") (pin "7") (pinfunction "GPB6_7") (pintype "bidirectional"))
    )
    (net (code "98") (name "/X095") (class "Default")
      (node (ref "A31") (pin "C1") (pinfunction "P$1_C1") (pintype "passive"))
      (node (ref "IC6") (pin "8") (pinfunction "GPB7_8") (pintype "bidirectional"))
    )
    (net (code "99") (name "/X096") (class "Default")
      (node (ref "A31") (pin "E1") (pinfunction "P$1_E1") (pintype "passive"))
      (node (ref "IC7") (pin "21") (pinfunction "GPA0_21") (pintype "bidirectional"))
    )
    (net (code "100") (name "/X097") (class "Default")
      (node (ref "A31") (pin "E2") (pinfunction "P$1_E2") (pintype "passive"))
      (node (ref "IC7") (pin "22") (pinfunction "GPA1_22") (pintype "bidirectional"))
    )
    (net (code "101") (name "/X098") (class "Default")
      (node (ref "A32") (pin "E1") (pinfunction "P$1_E1") (pintype "passive"))
      (node (ref "IC7") (pin "23") (pinfunction "GPA2_23") (pintype "bidirectional"))
    )
    (net (code "102") (name "/X099") (class "Default")
      (node (ref "A32") (pin "E2") (pinfunction "P$1_E2") (pintype "passive"))
      (node (ref "IC7") (pin "24") (pinfunction "GPA3_24") (pintype "bidirectional"))
    )
    (net (code "103") (name "/X100") (class "Default")
      (node (ref "A31") (pin "F1") (pinfunction "P$1_F1") (pintype "passive"))
      (node (ref "IC7") (pin "25") (pinfunction "GPA4_25") (pintype "bidirectional"))
    )
    (net (code "104") (name "/X101") (class "Default")
      (node (ref "A31") (pin "F2") (pinfunction "P$1_F2") (pintype "passive"))
      (node (ref "IC7") (pin "26") (pinfunction "GPA5_26") (pintype "bidirectional"))
    )
    (net (code "105") (name "/X102") (class "Default")
      (node (ref "A32") (pin "F1") (pinfunction "P$1_F1") (pintype "passive"))
      (node (ref "IC7") (pin "27") (pinfunction "GPA6_27") (pintype "bidirectional"))
    )
    (net (code "106") (name "/X103") (class "Default")
      (node (ref "A32") (pin "F2") (pinfunction "P$1_F2") (pintype "passive"))
      (node (ref "IC7") (pin "28") (pinfunction "GPA7_28") (pintype "bidirectional"))
    )
    (net (code "107") (name "/X104") (class "Default")
      (node (ref "A32") (pin "J2") (pinfunction "P$1_J2") (pintype "passive"))
      (node (ref "IC7") (pin "1") (pinfunction "GPB0_1") (pintype "bidirectional"))
    )
    (net (code "108") (name "/X105") (class "Default")
      (node (ref "A32") (pin "J1") (pinfunction "P$1_J1") (pintype "passive"))
      (node (ref "IC7") (pin "2") (pinfunction "GPB1_2") (pintype "bidirectional"))
    )
    (net (code "109") (name "/X106") (class "Default")
      (node (ref "A31") (pin "J2") (pinfunction "P$1_J2") (pintype "passive"))
      (node (ref "IC7") (pin "3") (pinfunction "GPB2_3") (pintype "bidirectional"))
    )
    (net (code "110") (name "/X107") (class "Default")
      (node (ref "A31") (pin "J1") (pinfunction "P$1_J1") (pintype "passive"))
      (node (ref "IC7") (pin "4") (pinfunction "GPB3_4") (pintype "bidirectional"))
    )
    (net (code "111") (name "/X108") (class "Default")
      (node (ref "A32") (pin "H2") (pinfunction "P$1_H2") (pintype "passive"))
      (node (ref "IC7") (pin "5") (pinfunction "GPB4_5") (pintype "bidirectional"))
    )
    (net (code "112") (name "/X109") (class "Default")
      (node (ref "A32") (pin "H1") (pinfunction "P$1_H1") (pintype "passive"))
      (node (ref "IC7") (pin "6") (pinfunction "GPB5_6") (pintype "bidirectional"))
    )
    (net (code "113") (name "/X110") (class "Default")
      (node (ref "A31") (pin "H2") (pinfunction "P$1_H2") (pintype "passive"))
      (node (ref "IC7") (pin "7") (pinfunction "GPB6_7") (pintype "bidirectional"))
    )
    (net (code "114") (name "/X111") (class "Default")
      (node (ref "A31") (pin "H1") (pinfunction "P$1_H1") (pintype "passive"))
      (node (ref "IC7") (pin "8") (pinfunction "GPB7_8") (pintype "bidirectional"))
    )
    (net (code "115") (name "/X112") (class "Default")
      (node (ref "A31") (pin "K1") (pinfunction "P$1_K1") (pintype "passive"))
      (node (ref "IC8") (pin "21") (pinfunction "GPA0_21") (pintype "bidirectional"))
    )
    (net (code "116") (name "/X113") (class "Default")
      (node (ref "A31") (pin "K2") (pinfunction "P$1_K2") (pintype "passive"))
      (node (ref "IC8") (pin "22") (pinfunction "GPA1_22") (pintype "bidirectional"))
    )
    (net (code "117") (name "/X114") (class "Default")
      (node (ref "A32") (pin "K1") (pinfunction "P$1_K1") (pintype "passive"))
      (node (ref "IC8") (pin "23") (pinfunction "GPA2_23") (pintype "bidirectional"))
    )
    (net (code "118") (name "/X115") (class "Default")
      (node (ref "A32") (pin "K2") (pinfunction "P$1_K2") (pintype "passive"))
      (node (ref "IC8") (pin "24") (pinfunction "GPA3_24") (pintype "bidirectional"))
    )
    (net (code "119") (name "/X116") (class "Default")
      (node (ref "A31") (pin "L1") (pinfunction "P$1_L1") (pintype "passive"))
      (node (ref "IC8") (pin "25") (pinfunction "GPA4_25") (pintype "bidirectional"))
    )
    (net (code "120") (name "/X117") (class "Default")
      (node (ref "A31") (pin "L2") (pinfunction "P$1_L2") (pintype "passive"))
      (node (ref "IC8") (pin "26") (pinfunction "GPA5_26") (pintype "bidirectional"))
    )
    (net (code "121") (name "/X118") (class "Default")
      (node (ref "A32") (pin "L1") (pinfunction "P$1_L1") (pintype "passive"))
      (node (ref "IC8") (pin "27") (pinfunction "GPA6_27") (pintype "bidirectional"))
    )
    (net (code "122") (name "/X119") (class "Default")
      (node (ref "A32") (pin "L2") (pinfunction "P$1_L2") (pintype "passive"))
      (node (ref "IC8") (pin "28") (pinfunction "GPA7_28") (pintype "bidirectional"))
    )
    (net (code "123") (name "/X120") (class "Default")
      (node (ref "A32") (pin "N2") (pinfunction "P$1_N2") (pintype "passive"))
      (node (ref "IC8") (pin "1") (pinfunction "GPB0_1") (pintype "bidirectional"))
    )
    (net (code "124") (name "/X121") (class "Default")
      (node (ref "A32") (pin "N1") (pinfunction "P$1_N1") (pintype "passive"))
      (node (ref "IC8") (pin "2") (pinfunction "GPB1_2") (pintype "bidirectional"))
    )
    (net (code "125") (name "/X122") (class "Default")
      (node (ref "A31") (pin "N2") (pinfunction "P$1_N2") (pintype "passive"))
      (node (ref "IC8") (pin "3") (pinfunction "GPB2_3") (pintype "bidirectional"))
    )
    (net (code "126") (name "/X123") (class "Default")
      (node (ref "A31") (pin "N1") (pinfunction "P$1_N1") (pintype "passive"))
      (node (ref "IC8") (pin "4") (pinfunction "GPB3_4") (pintype "bidirectional"))
    )
    (net (code "127") (name "/X124") (class "Default")
      (node (ref "A32") (pin "M2") (pinfunction "P$1_M2") (pintype "passive"))
      (node (ref "IC8") (pin "5") (pinfunction "GPB4_5") (pintype "bidirectional"))
    )
    (net (code "128") (name "/X125") (class "Default")
      (node (ref "A32") (pin "M1") (pinfunction "P$1_M1") (pintype "passive"))
      (node (ref "IC8") (pin "6") (pinfunction "GPB5_6") (pintype "bidirectional"))
    )
    (net (code "129") (name "/X126") (class "Default")
      (node (ref "A31") (pin "M2") (pinfunction "P$1_M2") (pintype "passive"))
      (node (ref "IC8") (pin "7") (pinfunction "GPB6_7") (pintype "bidirectional"))
    )
    (net (code "130") (name "/X127") (class "Default")
      (node (ref "A31") (pin "M1") (pinfunction "P$1_M1") (pintype "passive"))
      (node (ref "IC8") (pin "8") (pinfunction "GPB7_8") (pintype "bidirectional"))
    )
    (net (code "131") (name "/X128") (class "Default")
      (node (ref "A31") (pin "P1") (pinfunction "P$1_P1") (pintype "passive"))
      (node (ref "IC9") (pin "21") (pinfunction "GPA0_21") (pintype "bidirectional"))
    )
    (net (code "132") (name "/X129") (class "Default")
      (node (ref "A31") (pin "P2") (pinfunction "P$1_P2") (pintype "passive"))
      (node (ref "IC9") (pin "22") (pinfunction "GPA1_22") (pintype "bidirectional"))
    )
    (net (code "133") (name "/X130") (class "Default")
      (node (ref "A32") (pin "P1") (pinfunction "P$1_P1") (pintype "passive"))
      (node (ref "IC9") (pin "23") (pinfunction "GPA2_23") (pintype "bidirectional"))
    )
    (net (code "134") (name "/X131") (class "Default")
      (node (ref "A32") (pin "P2") (pinfunction "P$1_P2") (pintype "passive"))
      (node (ref "IC9") (pin "24") (pinfunction "GPA3_24") (pintype "bidirectional"))
    )
    (net (code "135") (name "/X132") (class "Default")
      (node (ref "A31") (pin "R1") (pinfunction "P$1_R1") (pintype "passive"))
      (node (ref "IC9") (pin "25") (pinfunction "GPA4_25") (pintype "bidirectional"))
    )
    (net (code "136") (name "/X133") (class "Default")
      (node (ref "A31") (pin "R2") (pinfunction "P$1_R2") (pintype "passive"))
      (node (ref "IC9") (pin "26") (pinfunction "GPA5_26") (pintype "bidirectional"))
    )
    (net (code "137") (name "/X134") (class "Default")
      (node (ref "A32") (pin "R1") (pinfunction "P$1_R1") (pintype "passive"))
      (node (ref "IC9") (pin "27") (pinfunction "GPA6_27") (pintype "bidirectional"))
    )
    (net (code "138") (name "/X135") (class "Default")
      (node (ref "A32") (pin "R2") (pinfunction "P$1_R2") (pintype "passive"))
      (node (ref "IC9") (pin "28") (pinfunction "GPA7_28") (pintype "bidirectional"))
    )
    (net (code "139") (name "/X136") (class "Default")
      (node (ref "A32") (pin "T2") (pinfunction "P$1_T2") (pintype "passive"))
      (node (ref "IC9") (pin "1") (pinfunction "GPB0_1") (pintype "bidirectional"))
    )
    (net (code "140") (name "/X137") (class "Default")
      (node (ref "A32") (pin "T1") (pinfunction "P$1_T1") (pintype "passive"))
      (node (ref "IC9") (pin "2") (pinfunction "GPB1_2") (pintype "bidirectional"))
    )
    (net (code "141") (name "/X138") (class "Default")
      (node (ref "A31") (pin "T2") (pinfunction "P$1_T2") (pintype "passive"))
      (node (ref "IC9") (pin "3") (pinfunction "GPB2_3") (pintype "bidirectional"))
    )
    (net (code "142") (name "/X139") (class "Default")
      (node (ref "A31") (pin "T1") (pinfunction "P$1_T1") (pintype "passive"))
      (node (ref "IC9") (pin "4") (pinfunction "GPB3_4") (pintype "bidirectional"))
    )
    (net (code "143") (name "/X140") (class "Default")
      (node (ref "A32") (pin "S2") (pinfunction "P$1_S2") (pintype "passive"))
      (node (ref "IC9") (pin "5") (pinfunction "GPB4_5") (pintype "bidirectional"))
    )
    (net (code "144") (name "/X141") (class "Default")
      (node (ref "A32") (pin "S1") (pinfunction "P$1_S1") (pintype "passive"))
      (node (ref "IC9") (pin "6") (pinfunction "GPB5_6") (pintype "bidirectional"))
    )
    (net (code "145") (name "/X142") (class "Default")
      (node (ref "A31") (pin "S2") (pinfunction "P$1_S2") (pintype "passive"))
      (node (ref "IC9") (pin "7") (pinfunction "GPB6_7") (pintype "bidirectional"))
    )
    (net (code "146") (name "/X143") (class "Default")
      (node (ref "A31") (pin "S1") (pinfunction "P$1_S1") (pintype "passive"))
      (node (ref "IC9") (pin "8") (pinfunction "GPB7_8") (pintype "bidirectional"))
    )
    (net (code "147") (name "/X144") (class "Default")
      (node (ref "A31") (pin "U1") (pinfunction "P$1_U1") (pintype "passive"))
      (node (ref "IC10") (pin "21") (pinfunction "GPA0_21") (pintype "bidirectional"))
    )
    (net (code "148") (name "/X145") (class "Default")
      (node (ref "A31") (pin "U2") (pinfunction "P$1_U2") (pintype "passive"))
      (node (ref "IC10") (pin "22") (pinfunction "GPA1_22") (pintype "bidirectional"))
    )
    (net (code "149") (name "/X146") (class "Default")
      (node (ref "A32") (pin "U1") (pinfunction "P$1_U1") (pintype "passive"))
      (node (ref "IC10") (pin "23") (pinfunction "GPA2_23") (pintype "bidirectional"))
    )
    (net (code "150") (name "/X147") (class "Default")
      (node (ref "A32") (pin "U2") (pinfunction "P$1_U2") (pintype "passive"))
      (node (ref "IC10") (pin "24") (pinfunction "GPA3_24") (pintype "bidirectional"))
    )
    (net (code "151") (name "/X148") (class "Default")
      (node (ref "A31") (pin "V1") (pinfunction "P$1_V1") (pintype "passive"))
      (node (ref "IC10") (pin "25") (pinfunction "GPA4_25") (pintype "bidirectional"))
    )
    (net (code "152") (name "/X149") (class "Default")
      (node (ref "A31") (pin "V2") (pinfunction "P$1_V2") (pintype "passive"))
      (node (ref "IC10") (pin "26") (pinfunction "GPA5_26") (pintype "bidirectional"))
    )
    (net (code "153") (name "/X150") (class "Default")
      (node (ref "A32") (pin "V1") (pinfunction "P$1_V1") (pintype "passive"))
      (node (ref "IC10") (pin "27") (pinfunction "GPA6_27") (pintype "bidirectional"))
    )
    (net (code "154") (name "/X151") (class "Default")
      (node (ref "A32") (pin "V2") (pinfunction "P$1_V2") (pintype "passive"))
      (node (ref "IC10") (pin "28") (pinfunction "GPA7_28") (pintype "bidirectional"))
    )
    (net (code "155") (name "/X152") (class "Default")
      (node (ref "IC10") (pin "1") (pinfunction "GPB0_1") (pintype "bidirectional"))
      (node (ref "OUT2") (pin "3") (pinfunction "3_3") (pintype "passive"))
    )
    (net (code "156") (name "/X153") (class "Default")
      (node (ref "IC10") (pin "2") (pinfunction "GPB1_2") (pintype "bidirectional"))
      (node (ref "OUT2") (pin "4") (pinfunction "4_4") (pintype "passive"))
    )
    (net (code "157") (name "/X154") (class "Default")
      (node (ref "IC10") (pin "3") (pinfunction "GPB2_3") (pintype "bidirectional"))
      (node (ref "OUT2") (pin "5") (pinfunction "5_5") (pintype "passive"))
    )
    (net (code "158") (name "/X155") (class "Default")
      (node (ref "IC10") (pin "4") (pinfunction "GPB3_4") (pintype "bidirectional"))
      (node (ref "OUT2") (pin "6") (pinfunction "6_6") (pintype "passive"))
    )
    (net (code "159") (name "/X156") (class "Default")
      (node (ref "IC10") (pin "5") (pinfunction "GPB4_5") (pintype "bidirectional"))
      (node (ref "OUT2") (pin "7") (pinfunction "7_7") (pintype "passive"))
    )
    (net (code "160") (name "/X157") (class "Default")
      (node (ref "IC10") (pin "6") (pinfunction "GPB5_6") (pintype "bidirectional"))
      (node (ref "OUT2") (pin "8") (pinfunction "8_8") (pintype "passive"))
    )
    (net (code "161") (name "/X158") (class "Default")
      (node (ref "IC10") (pin "7") (pinfunction "GPB6_7") (pintype "bidirectional"))
      (node (ref "OUT2") (pin "9") (pinfunction "9_9") (pintype "passive"))
    )
    (net (code "162") (name "/X159") (class "Default")
      (node (ref "IC10") (pin "8") (pinfunction "GPB7_8") (pintype "bidirectional"))
      (node (ref "OUT2") (pin "10") (pinfunction "10_10") (pintype "passive"))
    )
    (net (code "163") (name "GND") (class "Default")
      (node (ref "A30") (pin "D2") (pinfunction "P$1_D2") (pintype "passive"))
      (node (ref "A30") (pin "F2") (pinfunction "P$1_F2") (pintype "passive"))
      (node (ref "C1") (pin "1") (pinfunction "1_1") (pintype "passive"))
      (node (ref "C10") (pin "2") (pinfunction "2_2") (pintype "passive"))
      (node (ref "C11") (pin "2") (pinfunction "2_2") (pintype "passive"))
      (node (ref "C12") (pin "2") (pinfunction "2_2") (pintype "passive"))
      (node (ref "C13") (pin "2") (pinfunction "2_2") (pintype "passive"))
      (node (ref "C14") (pin "2") (pinfunction "2_2") (pintype "passive"))
      (node (ref "C2") (pin "1") (pinfunction "1_1") (pintype "passive"))
      (node (ref "C3") (pin "2") (pinfunction "2_2") (pintype "passive"))
      (node (ref "C4") (pin "2") (pinfunction "2_2") (pintype "passive"))
      (node (ref "C5") (pin "2") (pinfunction "2_2") (pintype "passive"))
      (node (ref "C6") (pin "2") (pinfunction "2_2") (pintype "passive"))
      (node (ref "C7") (pin "2") (pinfunction "2_2") (pintype "passive"))
      (node (ref "C8") (pin "2") (pinfunction "2_2") (pintype "passive"))
      (node (ref "C9") (pin "2") (pinfunction "2_2") (pintype "passive"))
      (node (ref "IC1") (pin "10") (pinfunction "VSS_10") (pintype "power_in"))
      (node (ref "IC1") (pin "15") (pinfunction "A0_15") (pintype "input"))
      (node (ref "IC1") (pin "16") (pinfunction "A1_16") (pintype "input"))
      (node (ref "IC1") (pin "17") (pinfunction "A2_17") (pintype "input"))
      (node (ref "IC10") (pin "10") (pinfunction "VSS_10") (pintype "power_in"))
      (node (ref "IC10") (pin "15") (pinfunction "A0_15") (pintype "input"))
      (node (ref "IC10") (pin "16") (pinfunction "A1_16") (pintype "input"))
      (node (ref "IC11") (pin "19") (pinfunction "VSS_19") (pintype "power_in"))
      (node (ref "IC11") (pin "8") (pinfunction "VSS_8") (pintype "power_in"))
      (node (ref "IC2") (pin "10") (pinfunction "VSS_10") (pintype "power_in"))
      (node (ref "IC2") (pin "16") (pinfunction "A1_16") (pintype "input"))
      (node (ref "IC2") (pin "17") (pinfunction "A2_17") (pintype "input"))
      (node (ref "IC3") (pin "10") (pinfunction "VSS_10") (pintype "power_in"))
      (node (ref "IC3") (pin "15") (pinfunction "A0_15") (pintype "input"))
      (node (ref "IC3") (pin "17") (pinfunction "A2_17") (pintype "input"))
      (node (ref "IC4") (pin "10") (pinfunction "VSS_10") (pintype "power_in"))
      (node (ref "IC4") (pin "17") (pinfunction "A2_17") (pintype "input"))
      (node (ref "IC5") (pin "10") (pinfunction "VSS_10") (pintype "power_in"))
      (node (ref "IC5") (pin "15") (pinfunction "A0_15") (pintype "input"))
      (node (ref "IC5") (pin "16") (pinfunction "A1_16") (pintype "input"))
      (node (ref "IC6") (pin "10") (pinfunction "VSS_10") (pintype "power_in"))
      (node (ref "IC6") (pin "15") (pinfunction "A0_15") (pintype "input"))
      (node (ref "IC6") (pin "16") (pinfunction "A1_16") (pintype "input"))
      (node (ref "IC6") (pin "17") (pinfunction "A2_17") (pintype "input"))
      (node (ref "IC7") (pin "10") (pinfunction "VSS_10") (pintype "power_in"))
      (node (ref "IC7") (pin "16") (pinfunction "A1_16") (pintype "input"))
      (node (ref "IC7") (pin "17") (pinfunction "A2_17") (pintype "input"))
      (node (ref "IC8") (pin "10") (pinfunction "VSS_10") (pintype "power_in"))
      (node (ref "IC8") (pin "15") (pinfunction "A0_15") (pintype "input"))
      (node (ref "IC8") (pin "17") (pinfunction "A2_17") (pintype "input"))
      (node (ref "IC9") (pin "10") (pinfunction "VSS_10") (pintype "power_in"))
      (node (ref "IC9") (pin "17") (pinfunction "A2_17") (pintype "input"))
      (node (ref "OUT1") (pin "1") (pinfunction "1_1") (pintype "passive"))
      (node (ref "OUT1") (pin "2") (pinfunction "2_2") (pintype "passive"))
      (node (ref "OUT2") (pin "1") (pinfunction "1_1") (pintype "passive"))
      (node (ref "OUT2") (pin "2") (pinfunction "2_2") (pintype "passive"))
      (node (ref "PWR") (pin "1") (pinfunction "1_1") (pintype "passive"))
      (node (ref "PWR") (pin "3") (pinfunction "3_3") (pintype "passive"))
      (node (ref "RS232") (pin "1") (pinfunction "1_1") (pintype "passive"))
    )
    (net (code "164") (name "Net-(DIAG-C)") (class "Default")
      (node (ref "DIAG") (pin "K") (pinfunction "C_K") (pintype "passive"))
      (node (ref "R2") (pin "2") (pinfunction "2_2") (pintype "passive"))
    )
    (net (code "165") (name "Net-(FAULT-C)") (class "Default")
      (node (ref "FAULT") (pin "K") (pinfunction "C_K") (pintype "passive"))
      (node (ref "R3") (pin "2") (pinfunction "2_2") (pintype "passive"))
    )
    (net (code "166") (name "Net-(IC1-SCK)") (class "Default")
      (node (ref "IC1") (pin "12") (pinfunction "SCK_12") (pintype "input"))
      (node (ref "IC10") (pin "12") (pinfunction "SCK_12") (pintype "input"))
      (node (ref "IC11") (pin "25") (pinfunction "RB4/AN11_25") (pintype "bidirectional"))
      (node (ref "IC2") (pin "12") (pinfunction "SCK_12") (pintype "input"))
      (node (ref "IC3") (pin "12") (pinfunction "SCK_12") (pintype "input"))
      (node (ref "IC4") (pin "12") (pinfunction "SCK_12") (pintype "input"))
      (node (ref "IC5") (pin "12") (pinfunction "SCK_12") (pintype "input"))
      (node (ref "IC6") (pin "12") (pinfunction "SCK_12") (pintype "input"))
      (node (ref "IC7") (pin "12") (pinfunction "SCK_12") (pintype "input"))
      (node (ref "IC8") (pin "12") (pinfunction "SCK_12") (pintype "input"))
      (node (ref "IC9") (pin "12") (pinfunction "SCK_12") (pintype "input"))
    )
    (net (code "167") (name "Net-(IC1-SI)") (class "Default")
      (node (ref "IC1") (pin "13") (pinfunction "SI_13") (pintype "input"))
      (node (ref "IC10") (pin "13") (pinfunction "SI_13") (pintype "input"))
      (node (ref "IC11") (pin "24") (pinfunction "RB3/AN9_24") (pintype "bidirectional"))
      (node (ref "IC2") (pin "13") (pinfunction "SI_13") (pintype "input"))
      (node (ref "IC3") (pin "13") (pinfunction "SI_13") (pintype "input"))
      (node (ref "IC4") (pin "13") (pinfunction "SI_13") (pintype "input"))
      (node (ref "IC5") (pin "13") (pinfunction "SI_13") (pintype "input"))
      (node (ref "IC6") (pin "13") (pinfunction "SI_13") (pintype "input"))
      (node (ref "IC7") (pin "13") (pinfunction "SI_13") (pintype "input"))
      (node (ref "IC8") (pin "13") (pinfunction "SI_13") (pintype "input"))
      (node (ref "IC9") (pin "13") (pinfunction "SI_13") (pintype "input"))
    )
    (net (code "168") (name "Net-(IC1-~{RESET})") (class "Default")
      (node (ref "IC1") (pin "18") (pinfunction "~{RESET}_18") (pintype "input"))
      (node (ref "IC10") (pin "18") (pinfunction "~{RESET}_18") (pintype "input"))
      (node (ref "IC11") (pin "26") (pinfunction "RB5/PGM_26") (pintype "bidirectional"))
      (node (ref "IC2") (pin "18") (pinfunction "~{RESET}_18") (pintype "input"))
      (node (ref "IC3") (pin "18") (pinfunction "~{RESET}_18") (pintype "input"))
      (node (ref "IC4") (pin "18") (pinfunction "~{RESET}_18") (pintype "input"))
      (node (ref "IC5") (pin "18") (pinfunction "~{RESET}_18") (pintype "input"))
      (node (ref "IC6") (pin "18") (pinfunction "~{RESET}_18") (pintype "input"))
      (node (ref "IC7") (pin "18") (pinfunction "~{RESET}_18") (pintype "input"))
      (node (ref "IC8") (pin "18") (pinfunction "~{RESET}_18") (pintype "input"))
      (node (ref "IC9") (pin "18") (pinfunction "~{RESET}_18") (pintype "input"))
    )
    (net (code "169") (name "Net-(IC11-MCLR{slash}VPP)") (class "Default")
      (node (ref "C3") (pin "1") (pinfunction "1_1") (pintype "passive"))
      (node (ref "IC11") (pin "1") (pinfunction "MCLR/VPP_1") (pintype "bidirectional"))
      (node (ref "R1") (pin "1") (pinfunction "1_1") (pintype "passive"))
    )
    (net (code "170") (name "Net-(IC11-OSC1)") (class "Default")
      (node (ref "C1") (pin "2") (pinfunction "2_2") (pintype "passive"))
      (node (ref "IC11") (pin "9") (pinfunction "OSC1_9") (pintype "bidirectional"))
      (node (ref "Q1") (pin "1") (pinfunction "1_1") (pintype "passive"))
    )
    (net (code "171") (name "Net-(IC11-OSC2)") (class "Default")
      (node (ref "C2") (pin "2") (pinfunction "2_2") (pintype "passive"))
      (node (ref "IC11") (pin "10") (pinfunction "OSC2_10") (pintype "bidirectional"))
      (node (ref "Q1") (pin "2") (pinfunction "2_2") (pintype "passive"))
    )
    (net (code "172") (name "Net-(IC11-RA0{slash}AN0)") (class "Default")
      (node (ref "IC11") (pin "2") (pinfunction "RA0/AN0_2") (pintype "bidirectional"))
      (node (ref "R3") (pin "1") (pinfunction "1_1") (pintype "passive"))
    )
    (net (code "173") (name "Net-(IC11-RA4{slash}AN4)") (class "Default")
      (node (ref "IC11") (pin "6") (pinfunction "RA4/AN4_6") (pintype "bidirectional"))
      (node (ref "R2") (pin "1") (pinfunction "1_1") (pintype "passive"))
    )
    (net (code "174") (name "Net-(IC11-RX{slash}RC7)") (class "Default")
      (node (ref "IC11") (pin "18") (pinfunction "RX/RC7_18") (pintype "input"))
      (node (ref "RS232") (pin "4") (pinfunction "4_4") (pintype "passive"))
    )
    (net (code "175") (name "Net-(IC11-TX{slash}RC6)") (class "Default")
      (node (ref "IC11") (pin "17") (pinfunction "TX/RC6_17") (pintype "bidirectional"))
      (node (ref "RS232") (pin "5") (pinfunction "5_5") (pintype "passive"))
    )
    (net (code "176") (name "Net-(JP1-Pad1)") (class "Default")
      (node (ref "JP1") (pin "1") (pinfunction "1_1") (pintype "passive"))
      (node (ref "RS232") (pin "3") (pinfunction "3_3") (pintype "passive"))
    )
    (net (code "177") (name "VDD") (class "Default")
      (node (ref "C10") (pin "1") (pinfunction "1_1") (pintype "passive"))
      (node (ref "C11") (pin "1") (pinfunction "1_1") (pintype "passive"))
      (node (ref "C12") (pin "1") (pinfunction "1_1") (pintype "passive"))
      (node (ref "C13") (pin "1") (pinfunction "1_1") (pintype "passive"))
      (node (ref "C14") (pin "1") (pinfunction "1_1") (pintype "passive"))
      (node (ref "C4") (pin "1") (pinfunction "1_1") (pintype "passive"))
      (node (ref "C5") (pin "1") (pinfunction "1_1") (pintype "passive"))
      (node (ref "C6") (pin "1") (pinfunction "1_1") (pintype "passive"))
      (node (ref "C7") (pin "1") (pinfunction "1_1") (pintype "passive"))
      (node (ref "C8") (pin "1") (pinfunction "1_1") (pintype "passive"))
      (node (ref "C9") (pin "1") (pinfunction "1_1") (pintype "passive"))
      (node (ref "DIAG") (pin "A") (pinfunction "A_A") (pintype "passive"))
      (node (ref "FAULT") (pin "A") (pinfunction "A_A") (pintype "passive"))
      (node (ref "IC1") (pin "9") (pinfunction "VDD_9") (pintype "power_in"))
      (node (ref "IC10") (pin "17") (pinfunction "A2_17") (pintype "input"))
      (node (ref "IC10") (pin "9") (pinfunction "VDD_9") (pintype "power_in"))
      (node (ref "IC11") (pin "20") (pinfunction "VDD_20") (pintype "power_in"))
      (node (ref "IC2") (pin "15") (pinfunction "A0_15") (pintype "input"))
      (node (ref "IC2") (pin "9") (pinfunction "VDD_9") (pintype "power_in"))
      (node (ref "IC3") (pin "16") (pinfunction "A1_16") (pintype "input"))
      (node (ref "IC3") (pin "9") (pinfunction "VDD_9") (pintype "power_in"))
      (node (ref "IC4") (pin "15") (pinfunction "A0_15") (pintype "input"))
      (node (ref "IC4") (pin "16") (pinfunction "A1_16") (pintype "input"))
      (node (ref "IC4") (pin "9") (pinfunction "VDD_9") (pintype "power_in"))
      (node (ref "IC5") (pin "17") (pinfunction "A2_17") (pintype "input"))
      (node (ref "IC5") (pin "9") (pinfunction "VDD_9") (pintype "power_in"))
      (node (ref "IC6") (pin "9") (pinfunction "VDD_9") (pintype "power_in"))
      (node (ref "IC7") (pin "15") (pinfunction "A0_15") (pintype "input"))
      (node (ref "IC7") (pin "9") (pinfunction "VDD_9") (pintype "power_in"))
      (node (ref "IC8") (pin "16") (pinfunction "A1_16") (pintype "input"))
      (node (ref "IC8") (pin "9") (pinfunction "VDD_9") (pintype "power_in"))
      (node (ref "IC9") (pin "15") (pinfunction "A0_15") (pintype "input"))
      (node (ref "IC9") (pin "16") (pinfunction "A1_16") (pintype "input"))
      (node (ref "IC9") (pin "9") (pinfunction "VDD_9") (pintype "power_in"))
      (node (ref "JP1") (pin "2") (pinfunction "2_2") (pintype "passive"))
      (node (ref "PWR") (pin "2") (pinfunction "2_2") (pintype "passive"))
      (node (ref "R1") (pin "2") (pinfunction "2_2") (pintype "passive"))
    )
    (net (code "178") (name "unconnected-(IC1-INTA-Pad20)") (class "Default")
      (node (ref "IC1") (pin "20") (pinfunction "INTA_20") (pintype "output"))
    )
    (net (code "179") (name "unconnected-(IC1-INTB-Pad19)") (class "Default")
      (node (ref "IC1") (pin "19") (pinfunction "INTB_19") (pintype "output"))
    )
    (net (code "180") (name "unconnected-(IC1-SO-Pad14)") (class "Default")
      (node (ref "IC1") (pin "14") (pinfunction "SO_14") (pintype "output"))
    )
    (net (code "181") (name "unconnected-(IC2-INTA-Pad20)") (class "Default")
      (node (ref "IC2") (pin "20") (pinfunction "INTA_20") (pintype "output"))
    )
    (net (code "182") (name "unconnected-(IC2-INTB-Pad19)") (class "Default")
      (node (ref "IC2") (pin "19") (pinfunction "INTB_19") (pintype "output"))
    )
    (net (code "183") (name "unconnected-(IC2-SO-Pad14)") (class "Default")
      (node (ref "IC2") (pin "14") (pinfunction "SO_14") (pintype "output"))
    )
    (net (code "184") (name "unconnected-(IC3-INTA-Pad20)") (class "Default")
      (node (ref "IC3") (pin "20") (pinfunction "INTA_20") (pintype "output"))
    )
    (net (code "185") (name "unconnected-(IC3-INTB-Pad19)") (class "Default")
      (node (ref "IC3") (pin "19") (pinfunction "INTB_19") (pintype "output"))
    )
    (net (code "186") (name "unconnected-(IC3-SO-Pad14)") (class "Default")
      (node (ref "IC3") (pin "14") (pinfunction "SO_14") (pintype "output"))
    )
    (net (code "187") (name "unconnected-(IC4-INTA-Pad20)") (class "Default")
      (node (ref "IC4") (pin "20") (pinfunction "INTA_20") (pintype "output"))
    )
    (net (code "188") (name "unconnected-(IC4-INTB-Pad19)") (class "Default")
      (node (ref "IC4") (pin "19") (pinfunction "INTB_19") (pintype "output"))
    )
    (net (code "189") (name "unconnected-(IC4-SO-Pad14)") (class "Default")
      (node (ref "IC4") (pin "14") (pinfunction "SO_14") (pintype "output"))
    )
    (net (code "190") (name "unconnected-(IC5-INTA-Pad20)") (class "Default")
      (node (ref "IC5") (pin "20") (pinfunction "INTA_20") (pintype "output"))
    )
    (net (code "191") (name "unconnected-(IC5-INTB-Pad19)") (class "Default")
      (node (ref "IC5") (pin "19") (pinfunction "INTB_19") (pintype "output"))
    )
    (net (code "192") (name "unconnected-(IC5-SO-Pad14)") (class "Default")
      (node (ref "IC5") (pin "14") (pinfunction "SO_14") (pintype "output"))
    )
    (net (code "193") (name "unconnected-(IC6-INTA-Pad20)") (class "Default")
      (node (ref "IC6") (pin "20") (pinfunction "INTA_20") (pintype "output"))
    )
    (net (code "194") (name "unconnected-(IC6-INTB-Pad19)") (class "Default")
      (node (ref "IC6") (pin "19") (pinfunction "INTB_19") (pintype "output"))
    )
    (net (code "195") (name "unconnected-(IC6-SO-Pad14)") (class "Default")
      (node (ref "IC6") (pin "14") (pinfunction "SO_14") (pintype "output"))
    )
    (net (code "196") (name "unconnected-(IC7-INTA-Pad20)") (class "Default")
      (node (ref "IC7") (pin "20") (pinfunction "INTA_20") (pintype "output"))
    )
    (net (code "197") (name "unconnected-(IC7-INTB-Pad19)") (class "Default")
      (node (ref "IC7") (pin "19") (pinfunction "INTB_19") (pintype "output"))
    )
    (net (code "198") (name "unconnected-(IC7-SO-Pad14)") (class "Default")
      (node (ref "IC7") (pin "14") (pinfunction "SO_14") (pintype "output"))
    )
    (net (code "199") (name "unconnected-(IC8-INTA-Pad20)") (class "Default")
      (node (ref "IC8") (pin "20") (pinfunction "INTA_20") (pintype "output"))
    )
    (net (code "200") (name "unconnected-(IC8-INTB-Pad19)") (class "Default")
      (node (ref "IC8") (pin "19") (pinfunction "INTB_19") (pintype "output"))
    )
    (net (code "201") (name "unconnected-(IC8-SO-Pad14)") (class "Default")
      (node (ref "IC8") (pin "14") (pinfunction "SO_14") (pintype "output"))
    )
    (net (code "202") (name "unconnected-(IC9-INTA-Pad20)") (class "Default")
      (node (ref "IC9") (pin "20") (pinfunction "INTA_20") (pintype "output"))
    )
    (net (code "203") (name "unconnected-(IC9-INTB-Pad19)") (class "Default")
      (node (ref "IC9") (pin "19") (pinfunction "INTB_19") (pintype "output"))
    )
    (net (code "204") (name "unconnected-(IC9-SO-Pad14)") (class "Default")
      (node (ref "IC9") (pin "14") (pinfunction "SO_14") (pintype "output"))
    )
    (net (code "205") (name "unconnected-(IC10-INTA-Pad20)") (class "Default")
      (node (ref "IC10") (pin "20") (pinfunction "INTA_20") (pintype "output"))
    )
    (net (code "206") (name "unconnected-(IC10-INTB-Pad19)") (class "Default")
      (node (ref "IC10") (pin "19") (pinfunction "INTB_19") (pintype "output"))
    )
    (net (code "207") (name "unconnected-(IC10-SO-Pad14)") (class "Default")
      (node (ref "IC10") (pin "14") (pinfunction "SO_14") (pintype "output"))
    )
    (net (code "208") (name "unconnected-(IC11-RA1{slash}AN1-Pad3)") (class "Default")
      (node (ref "IC11") (pin "3") (pinfunction "RA1/AN1_3") (pintype "bidirectional"))
    )
    (net (code "209") (name "unconnected-(IC11-RA2{slash}AN2-Pad4)") (class "Default")
      (node (ref "IC11") (pin "4") (pinfunction "RA2/AN2_4") (pintype "bidirectional"))
    )
    (net (code "210") (name "unconnected-(IC11-RA3{slash}AN3-Pad5)") (class "Default")
      (node (ref "IC11") (pin "5") (pinfunction "RA3/AN3_5") (pintype "bidirectional"))
    )
    (net (code "211") (name "unconnected-(IC11-RA5{slash}AN4-Pad7)") (class "Default")
      (node (ref "IC11") (pin "7") (pinfunction "RA5/AN4_7") (pintype "bidirectional"))
    )
    (net (code "212") (name "unconnected-(IC11-RB0{slash}INT0-Pad21)") (class "Default")
      (node (ref "IC11") (pin "21") (pinfunction "RB0/INT0_21") (pintype "bidirectional"))
    )
    (net (code "213") (name "unconnected-(IC11-RB1{slash}INT1{slash}AN10-Pad22)") (class "Default")
      (node (ref "IC11") (pin "22") (pinfunction "RB1/INT1/AN10_22") (pintype "bidirectional"))
    )
    (net (code "214") (name "unconnected-(IC11-RB2{slash}INT2{slash}AN8-Pad23)") (class "Default")
      (node (ref "IC11") (pin "23") (pinfunction "RB2/INT2/AN8_23") (pintype "bidirectional"))
    )
    (net (code "215") (name "unconnected-(IC11-RC0-Pad11)") (class "Default")
      (node (ref "IC11") (pin "11") (pinfunction "RC0_11") (pintype "bidirectional"))
    )
    (net (code "216") (name "unconnected-(IC11-RC1-Pad12)") (class "Default")
      (node (ref "IC11") (pin "12") (pinfunction "RC1_12") (pintype "bidirectional"))
    )
    (net (code "217") (name "unconnected-(IC11-RC2-Pad13)") (class "Default")
      (node (ref "IC11") (pin "13") (pinfunction "RC2_13") (pintype "bidirectional"))
    )
    (net (code "218") (name "unconnected-(IC11-RC4{slash}D--Pad15)") (class "Default")
      (node (ref "IC11") (pin "15") (pinfunction "RC4/D-_15") (pintype "bidirectional"))
    )
    (net (code "219") (name "unconnected-(IC11-RC5{slash}D+-Pad16)") (class "Default")
      (node (ref "IC11") (pin "16") (pinfunction "RC5/D+_16") (pintype "bidirectional"))
    )
    (net (code "220") (name "unconnected-(IC11-V-USB-Pad14)") (class "Default")
      (node (ref "IC11") (pin "14") (pinfunction "V-USB_14") (pintype "bidirectional"))
    )
    (net (code "221") (name "unconnected-(RS232-Pad2)") (class "Default")
      (node (ref "RS232") (pin "2") (pinfunction "2_2") (pintype "passive"))
    )
    (net (code "222") (name "unconnected-(RS232-Pad6)") (class "Default")
      (node (ref "RS232") (pin "6") (pinfunction "6_6") (pintype "passive"))
    )
  )
)
